# VSWR_meter1.net
KiCad netlist of a schematic drawn in EAGLE
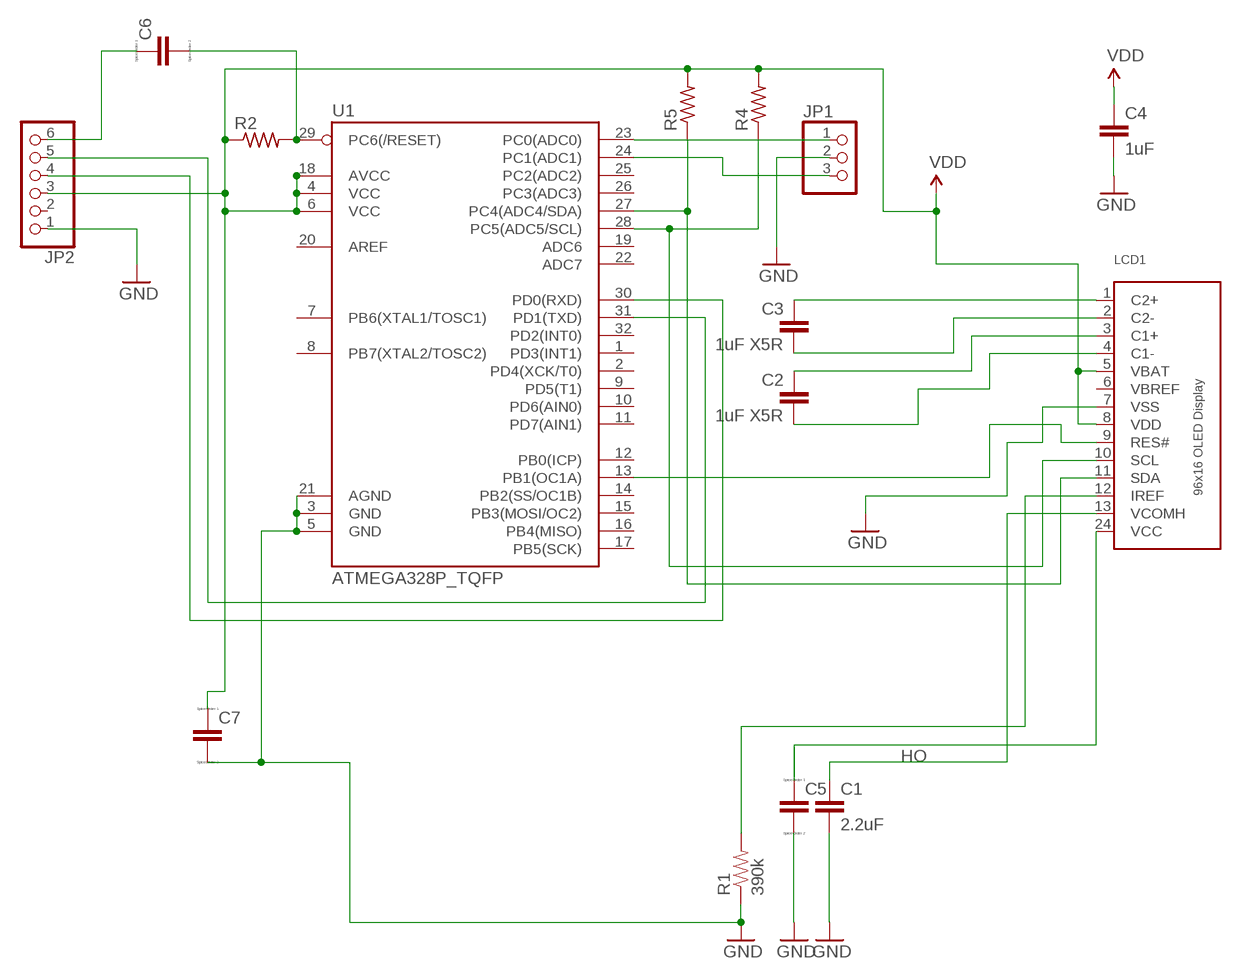
[diagram p0: schematic, sheet 1]

(export (version "E")
  (design (tool "Eeschema 10.0.6"))
  (components
    (comp (ref "C1")
      (value "2.2uF")
      (footprint "eagle-import:0805")
      (libsource (lib "eagle-import") (part "CAP0805"))
    )
    (comp (ref "C2")
      (value "1uF X5R")
      (footprint "eagle-import:0805")
      (libsource (lib "eagle-import") (part "CAP0805"))
    )
    (comp (ref "C3")
      (value "1uF X5R")
      (footprint "eagle-import:0805")
      (libsource (lib "eagle-import") (part "CAP0805"))
    )
    (comp (ref "C4")
      (value "1uF")
      (footprint "eagle-import:0603-CAP")
      (libsource (lib "eagle-import") (part "CAP0603-CAP"))
    )
    (comp (ref "C5")
      (value "CC0603")
      (footprint "eagle-import:C0603")
      (libsource (lib "eagle-import") (part "CC0603"))
    )
    (comp (ref "C6")
      (value "CC0603")
      (footprint "eagle-import:C0603")
      (libsource (lib "eagle-import") (part "CC0603"))
    )
    (comp (ref "C7")
      (value "CC0603")
      (footprint "eagle-import:C0603")
      (libsource (lib "eagle-import") (part "CC0603"))
    )
    (comp (ref "JP1")
      (value "HEADER-1X3")
      (footprint "eagle-import:1X03_OVAL")
      (libsource (lib "eagle-import") (part "HEADER-1X3"))
    )
    (comp (ref "JP2")
      (value "HEADER-1X6")
      (footprint "eagle-import:1X06_OVAL")
      (libsource (lib "eagle-import") (part "HEADER-1X6"))
    )
    (comp (ref "LCD1")
      (value "DISP_OLED_UG-9616GLBBG02")
      (footprint "eagle-import:UG-9616GLBBG02_0.65MM_WRAPAROUND")
      (libsource (lib "eagle-import") (part "DISP_OLED_UG-9616GLBBG02"))
    )
    (comp (ref "R1")
      (value "390k")
      (footprint "eagle-import:0603-RES")
      (libsource (lib "eagle-import") (part "RESISTOR0603-RES"))
    )
    (comp (ref "R2")
      (value "R-US_R0603")
      (footprint "eagle-import:R0603")
      (libsource (lib "eagle-import") (part "R-US_R0603"))
    )
    (comp (ref "R4")
      (value "R-US_R0603")
      (footprint "eagle-import:R0603")
      (libsource (lib "eagle-import") (part "R-US_R0603"))
    )
    (comp (ref "R5")
      (value "R-US_R0603")
      (footprint "eagle-import:R0603")
      (libsource (lib "eagle-import") (part "R-US_R0603"))
    )
    (comp (ref "U1")
      (value "ATMEGA328P_TQFP")
      (footprint "eagle-import:TQFP32-08")
      (libsource (lib "eagle-import") (part "ATMEGA328P_TQFP"))
    )
  )
  (nets
    (net (code "1") (name "/HO") (class "Default")
      (node (ref "C1") (pin "1") (pinfunction "1_1") (pintype "passive"))
      (node (ref "LCD1") (pin "13") (pinfunction "VCOMH_13") (pintype "bidirectional"))
    )
    (net (code "2") (name "GND") (class "Default")
      (node (ref "C1") (pin "2") (pinfunction "2_2") (pintype "passive"))
      (node (ref "C4") (pin "2") (pinfunction "2_2") (pintype "passive"))
      (node (ref "C5") (pin "2") (pinfunction "2_2") (pintype "passive"))
      (node (ref "C7") (pin "2") (pinfunction "2_2") (pintype "passive"))
      (node (ref "JP1") (pin "2") (pinfunction "2_2") (pintype "passive"))
      (node (ref "JP2") (pin "1") (pinfunction "1_1") (pintype "passive"))
      (node (ref "LCD1") (pin "7") (pinfunction "VSS_7") (pintype "bidirectional"))
      (node (ref "R1") (pin "1") (pinfunction "1_1") (pintype "passive"))
      (node (ref "U1") (pin "21") (pinfunction "AGND_21") (pintype "bidirectional"))
      (node (ref "U1") (pin "3") (pinfunction "GND_3") (pintype "bidirectional"))
      (node (ref "U1") (pin "5") (pinfunction "GND_5") (pintype "bidirectional"))
    )
    (net (code "3") (name "Net-(C6-Pad1)") (class "Default")
      (node (ref "C6") (pin "1") (pinfunction "1_1") (pintype "passive"))
      (node (ref "JP2") (pin "6") (pinfunction "6_6") (pintype "passive"))
    )
    (net (code "4") (name "Net-(LCD1-C1+)") (class "Default")
      (node (ref "C2") (pin "1") (pinfunction "1_1") (pintype "passive"))
      (node (ref "LCD1") (pin "3") (pinfunction "C1+_3") (pintype "bidirectional"))
    )
    (net (code "5") (name "Net-(LCD1-C1-)") (class "Default")
      (node (ref "C2") (pin "2") (pinfunction "2_2") (pintype "passive"))
      (node (ref "LCD1") (pin "4") (pinfunction "C1-_4") (pintype "bidirectional"))
    )
    (net (code "6") (name "Net-(LCD1-C2+)") (class "Default")
      (node (ref "C3") (pin "1") (pinfunction "1_1") (pintype "passive"))
      (node (ref "LCD1") (pin "1") (pinfunction "C2+_1") (pintype "bidirectional"))
    )
    (net (code "7") (name "Net-(LCD1-C2-)") (class "Default")
      (node (ref "C3") (pin "2") (pinfunction "2_2") (pintype "passive"))
      (node (ref "LCD1") (pin "2") (pinfunction "C2-_2") (pintype "bidirectional"))
    )
    (net (code "8") (name "Net-(LCD1-IREF)") (class "Default")
      (node (ref "LCD1") (pin "12") (pinfunction "IREF_12") (pintype "bidirectional"))
      (node (ref "R1") (pin "2") (pinfunction "2_2") (pintype "passive"))
    )
    (net (code "9") (name "Net-(LCD1-RES#)") (class "Default")
      (node (ref "LCD1") (pin "9") (pinfunction "RES#_9") (pintype "bidirectional"))
      (node (ref "U1") (pin "13") (pinfunction "PB1(OC1A)_13") (pintype "bidirectional"))
    )
    (net (code "10") (name "Net-(LCD1-SCL)") (class "Default")
      (node (ref "LCD1") (pin "10") (pinfunction "SCL_10") (pintype "bidirectional"))
      (node (ref "R4") (pin "1") (pinfunction "1_1") (pintype "passive"))
      (node (ref "U1") (pin "28") (pinfunction "PC5(ADC5/SCL)_28") (pintype "bidirectional"))
    )
    (net (code "11") (name "Net-(LCD1-SDA)") (class "Default")
      (node (ref "LCD1") (pin "11") (pinfunction "SDA_11") (pintype "bidirectional"))
      (node (ref "R5") (pin "1") (pinfunction "1_1") (pintype "passive"))
      (node (ref "U1") (pin "27") (pinfunction "PC4(ADC4/SDA)_27") (pintype "bidirectional"))
    )
    (net (code "12") (name "Net-(LCD1-VCC)") (class "Default")
      (node (ref "C5") (pin "1") (pinfunction "1_1") (pintype "passive"))
      (node (ref "LCD1") (pin "24") (pinfunction "VCC_24") (pintype "bidirectional"))
    )
    (net (code "13") (name "Net-(U1-PC0(ADC0))") (class "Default")
      (node (ref "JP1") (pin "1") (pinfunction "1_1") (pintype "passive"))
      (node (ref "U1") (pin "23") (pinfunction "PC0(ADC0)_23") (pintype "bidirectional"))
    )
    (net (code "14") (name "Net-(U1-PC1(ADC1))") (class "Default")
      (node (ref "JP1") (pin "3") (pinfunction "3_3") (pintype "passive"))
      (node (ref "U1") (pin "24") (pinfunction "PC1(ADC1)_24") (pintype "bidirectional"))
    )
    (net (code "15") (name "Net-(U1-PC6({slash}RESET))") (class "Default")
      (node (ref "C6") (pin "2") (pinfunction "2_2") (pintype "passive"))
      (node (ref "R2") (pin "2") (pinfunction "2_2") (pintype "passive"))
      (node (ref "U1") (pin "29") (pinfunction "PC6(/RESET)_29") (pintype "bidirectional"))
    )
    (net (code "16") (name "Net-(U1-PD0(RXD))") (class "Default")
      (node (ref "JP2") (pin "4") (pinfunction "4_4") (pintype "passive"))
      (node (ref "U1") (pin "30") (pinfunction "PD0(RXD)_30") (pintype "bidirectional"))
    )
    (net (code "17") (name "Net-(U1-PD1(TXD))") (class "Default")
      (node (ref "JP2") (pin "5") (pinfunction "5_5") (pintype "passive"))
      (node (ref "U1") (pin "31") (pinfunction "PD1(TXD)_31") (pintype "bidirectional"))
    )
    (net (code "18") (name "VDD") (class "Default")
      (node (ref "C4") (pin "1") (pinfunction "1_1") (pintype "passive"))
      (node (ref "C7") (pin "1") (pinfunction "1_1") (pintype "passive"))
      (node (ref "JP2") (pin "3") (pinfunction "3_3") (pintype "passive"))
      (node (ref "LCD1") (pin "5") (pinfunction "VBAT_5") (pintype "bidirectional"))
      (node (ref "LCD1") (pin "8") (pinfunction "VDD_8") (pintype "bidirectional"))
      (node (ref "R2") (pin "1") (pinfunction "1_1") (pintype "passive"))
      (node (ref "R4") (pin "2") (pinfunction "2_2") (pintype "passive"))
      (node (ref "R5") (pin "2") (pinfunction "2_2") (pintype "passive"))
      (node (ref "U1") (pin "18") (pinfunction "AVCC_18") (pintype "bidirectional"))
      (node (ref "U1") (pin "4") (pinfunction "VCC_4") (pintype "bidirectional"))
      (node (ref "U1") (pin "6") (pinfunction "VCC_6") (pintype "bidirectional"))
    )
    (net (code "19") (name "unconnected-(JP2-Pad2)") (class "Default")
      (node (ref "JP2") (pin "2") (pinfunction "2_2") (pintype "passive"))
    )
    (net (code "20") (name "unconnected-(LCD1-VBREF-Pad6)") (class "Default")
      (node (ref "LCD1") (pin "6") (pinfunction "VBREF_6") (pintype "bidirectional"))
    )
    (net (code "21") (name "unconnected-(U1-ADC6-Pad19)") (class "Default")
      (node (ref "U1") (pin "19") (pinfunction "ADC6_19") (pintype "bidirectional"))
    )
    (net (code "22") (name "unconnected-(U1-ADC7-Pad22)") (class "Default")
      (node (ref "U1") (pin "22") (pinfunction "ADC7_22") (pintype "bidirectional"))
    )
    (net (code "23") (name "unconnected-(U1-AREF-Pad20)") (class "Default")
      (node (ref "U1") (pin "20") (pinfunction "AREF_20") (pintype "bidirectional"))
    )
    (net (code "24") (name "unconnected-(U1-PB0(ICP)-Pad12)") (class "Default")
      (node (ref "U1") (pin "12") (pinfunction "PB0(ICP)_12") (pintype "bidirectional"))
    )
    (net (code "25") (name "unconnected-(U1-PB2(SS{slash}OC1B)-Pad14)") (class "Default")
      (node (ref "U1") (pin "14") (pinfunction "PB2(SS/OC1B)_14") (pintype "bidirectional"))
    )
    (net (code "26") (name "unconnected-(U1-PB3(MOSI{slash}OC2)-Pad15)") (class "Default")
      (node (ref "U1") (pin "15") (pinfunction "PB3(MOSI/OC2)_15") (pintype "bidirectional"))
    )
    (net (code "27") (name "unconnected-(U1-PB4(MISO)-Pad16)") (class "Default")
      (node (ref "U1") (pin "16") (pinfunction "PB4(MISO)_16") (pintype "bidirectional"))
    )
    (net (code "28") (name "unconnected-(U1-PB5(SCK)-Pad17)") (class "Default")
      (node (ref "U1") (pin "17") (pinfunction "PB5(SCK)_17") (pintype "bidirectional"))
    )
    (net (code "29") (name "unconnected-(U1-PB6(XTAL1{slash}TOSC1)-Pad7)") (class "Default")
      (node (ref "U1") (pin "7") (pinfunction "PB6(XTAL1/TOSC1)_7") (pintype "bidirectional"))
    )
    (net (code "30") (name "unconnected-(U1-PB7(XTAL2{slash}TOSC2)-Pad8)") (class "Default")
      (node (ref "U1") (pin "8") (pinfunction "PB7(XTAL2/TOSC2)_8") (pintype "bidirectional"))
    )
    (net (code "31") (name "unconnected-(U1-PC2(ADC2)-Pad25)") (class "Default")
      (node (ref "U1") (pin "25") (pinfunction "PC2(ADC2)_25") (pintype "bidirectional"))
    )
    (net (code "32") (name "unconnected-(U1-PC3(ADC3)-Pad26)") (class "Default")
      (node (ref "U1") (pin "26") (pinfunction "PC3(ADC3)_26") (pintype "bidirectional"))
    )
    (net (code "33") (name "unconnected-(U1-PD2(INT0)-Pad32)") (class "Default")
      (node (ref "U1") (pin "32") (pinfunction "PD2(INT0)_32") (pintype "bidirectional"))
    )
    (net (code "34") (name "unconnected-(U1-PD3(INT1)-Pad1)") (class "Default")
      (node (ref "U1") (pin "1") (pinfunction "PD3(INT1)_1") (pintype "bidirectional"))
    )
    (net (code "35") (name "unconnected-(U1-PD4(XCK{slash}T0)-Pad2)") (class "Default")
      (node (ref "U1") (pin "2") (pinfunction "PD4(XCK/T0)_2") (pintype "bidirectional"))
    )
    (net (code "36") (name "unconnected-(U1-PD5(T1)-Pad9)") (class "Default")
      (node (ref "U1") (pin "9") (pinfunction "PD5(T1)_9") (pintype "bidirectional"))
    )
    (net (code "37") (name "unconnected-(U1-PD6(AIN0)-Pad10)") (class "Default")
      (node (ref "U1") (pin "10") (pinfunction "PD6(AIN0)_10") (pintype "bidirectional"))
    )
    (net (code "38") (name "unconnected-(U1-PD7(AIN1)-Pad11)") (class "Default")
      (node (ref "U1") (pin "11") (pinfunction "PD7(AIN1)_11") (pintype "bidirectional"))
    )
  )
)
